# keyboard.net
KiCad netlist of a schematic drawn in EAGLE
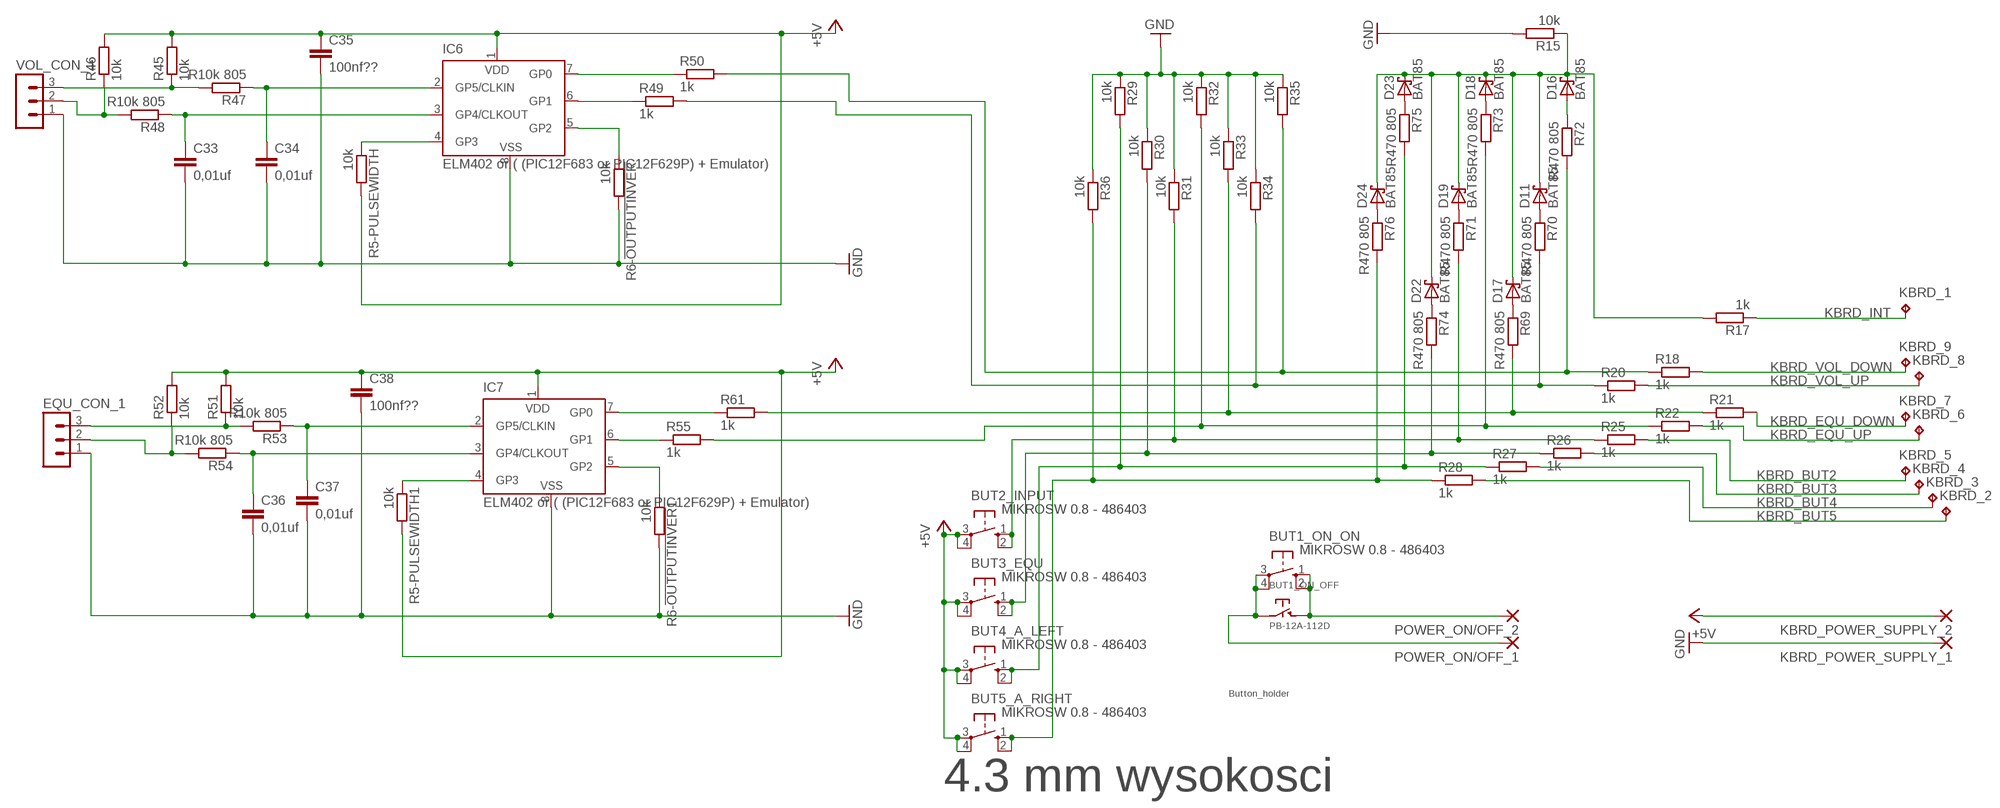
[diagram p0: schematic, sheet 1]

(export (version "E")
  (design (tool "Eeschema 10.0.6"))
  (components
    (comp (ref "BUT1_ON_OFF")
      (value "PB-12A-112D")
      (footprint "eagle-import:PB-12A-112D")
      (libsource (lib "eagle-import") (part "PB-12A-112D"))
    )
    (comp (ref "BUT1_ON_ON")
      (value "MIKROSW 0.8 - 486403")
      (footprint "eagle-import:B3F-10XX")
      (fields
        (field (name "MPN") "B3F-1000")
        (field (name "MF") "OMRON ELECTRONIC COMPONENTS")
        (field (name "MPN_1") "B3F-1000")
        (field (name "OC_FARNELL") "176432")
        (field (name "OC_NEWARK") "36M3542")
      )
      (libsource (lib "eagle-import") (part "10-XX"))
    )
    (comp (ref "BUT2_INPUT")
      (value "MIKROSW 0.8 - 486403")
      (footprint "eagle-import:B3F-10XX")
      (fields
        (field (name "MPN") "B3F-1000")
        (field (name "MF") "OMRON ELECTRONIC COMPONENTS")
        (field (name "MPN_1") "B3F-1000")
        (field (name "OC_FARNELL") "176432")
      )
      (libsource (lib "eagle-import") (part "10-XX"))
    )
    (comp (ref "BUT3_EQU")
      (value "MIKROSW 0.8 - 486403")
      (footprint "eagle-import:B3F-10XX")
      (fields
        (field (name "MPN") "B3F-1000")
        (field (name "MF") "OMRON ELECTRONIC COMPONENTS")
        (field (name "MPN_1") "B3F-1000")
        (field (name "OC_FARNELL") "176432")
      )
      (libsource (lib "eagle-import") (part "10-XX"))
    )
    (comp (ref "BUT4_A_LEFT")
      (value "MIKROSW 0.8 - 486403")
      (footprint "eagle-import:B3F-10XX")
      (fields
        (field (name "MPN") "B3F-1000")
        (field (name "MF") "OMRON ELECTRONIC COMPONENTS")
        (field (name "MPN_1") "B3F-1000")
        (field (name "OC_FARNELL") "176432")
      )
      (libsource (lib "eagle-import") (part "10-XX"))
    )
    (comp (ref "BUT5_A_RIGHT")
      (value "MIKROSW 0.8 - 486403")
      (footprint "eagle-import:B3F-10XX")
      (fields
        (field (name "MPN") "B3F-1000")
        (field (name "MF") "OMRON ELECTRONIC COMPONENTS")
        (field (name "MPN_1") "B3F-1000")
        (field (name "OC_FARNELL") "176432")
      )
      (libsource (lib "eagle-import") (part "10-XX"))
    )
    (comp (ref "C33")
      (value "0,01uf")
      (footprint "eagle-import:C0805")
      (libsource (lib "eagle-import") (part "C-EUC0805"))
    )
    (comp (ref "C34")
      (value "0,01uf")
      (footprint "eagle-import:C0805")
      (libsource (lib "eagle-import") (part "C-EUC0805"))
    )
    (comp (ref "C35")
      (value "100nf??")
      (footprint "eagle-import:C0805")
      (libsource (lib "eagle-import") (part "C-EUC0805"))
    )
    (comp (ref "C36")
      (value "0,01uf")
      (footprint "eagle-import:C0805")
      (libsource (lib "eagle-import") (part "C-EUC0805"))
    )
    (comp (ref "C37")
      (value "0,01uf")
      (footprint "eagle-import:C0805")
      (libsource (lib "eagle-import") (part "C-EUC0805"))
    )
    (comp (ref "C38")
      (value "100nf??")
      (footprint "eagle-import:C0805")
      (libsource (lib "eagle-import") (part "C-EUC0805"))
    )
    (comp (ref "D11")
      (value "BAT85")
      (footprint "eagle-import:DO34-5")
      (libsource (lib "eagle-import") (part "BAT85DO34-5"))
    )
    (comp (ref "D16")
      (value "BAT85")
      (footprint "eagle-import:DO34-5")
      (libsource (lib "eagle-import") (part "BAT85DO34-5"))
    )
    (comp (ref "D17")
      (value "BAT85")
      (footprint "eagle-import:DO34-5")
      (libsource (lib "eagle-import") (part "BAT85DO34-5"))
    )
    (comp (ref "D18")
      (value "BAT85")
      (footprint "eagle-import:DO34-5")
      (libsource (lib "eagle-import") (part "BAT85DO34-5"))
    )
    (comp (ref "D19")
      (value "BAT85")
      (footprint "eagle-import:DO34-5")
      (libsource (lib "eagle-import") (part "BAT85DO34-5"))
    )
    (comp (ref "D22")
      (value "BAT85")
      (footprint "eagle-import:DO34-5")
      (libsource (lib "eagle-import") (part "BAT85DO34-5"))
    )
    (comp (ref "D23")
      (value "BAT85")
      (footprint "eagle-import:DO34-5")
      (libsource (lib "eagle-import") (part "BAT85DO34-5"))
    )
    (comp (ref "D24")
      (value "BAT85")
      (footprint "eagle-import:DO34-5")
      (libsource (lib "eagle-import") (part "BAT85DO34-5"))
    )
    (comp (ref "EQU_CON_1")
      (value "MA03-1")
      (footprint "eagle-import:MA03-1")
      (fields (field (name "OC_FARNELL") "unknown"))
      (libsource (lib "eagle-import") (part "MA03-1"))
    )
    (comp (ref "IC6")
      (value "ELM402 or ( (PIC12F683 or PIC12F629P) + Emulator)")
      (footprint "eagle-import:DIL8")
      (fields
        (field (name "MF") "MICROCHIP")
        (field (name "MPN") "PIC12F629-I/P")
        (field (name "MF_1") "MICROCHIP")
        (field (name "MPN_1") "PIC12F629-E/P")
        (field (name "OC_FARNELL") "1292253")
      )
      (libsource (lib "eagle-import") (part "PIC12F6P29"))
    )
    (comp (ref "IC7")
      (value "ELM402 or ( (PIC12F683 or PIC12F629P) + Emulator)")
      (footprint "eagle-import:DIL8")
      (fields
        (field (name "MF") "MICROCHIP")
        (field (name "MPN") "PIC12F629-I/P")
        (field (name "MF_1") "MICROCHIP")
        (field (name "MPN_1") "PIC12F629-E/P")
        (field (name "OC_FARNELL") "1292253")
      )
      (libsource (lib "eagle-import") (part "PIC12F6P29"))
    )
    (comp (ref "KBRD_1")
      (value "TPPAD1-13Y")
      (footprint "eagle-import:P1-13Y")
      (libsource (lib "eagle-import") (part "TPPAD1-13Y"))
    )
    (comp (ref "KBRD_2")
      (value "TPPAD1-13Y")
      (footprint "eagle-import:P1-13Y")
      (libsource (lib "eagle-import") (part "TPPAD1-13Y"))
    )
    (comp (ref "KBRD_3")
      (value "TPPAD1-13Y")
      (footprint "eagle-import:P1-13Y")
      (libsource (lib "eagle-import") (part "TPPAD1-13Y"))
    )
    (comp (ref "KBRD_4")
      (value "TPPAD1-13Y")
      (footprint "eagle-import:P1-13Y")
      (libsource (lib "eagle-import") (part "TPPAD1-13Y"))
    )
    (comp (ref "KBRD_5")
      (value "TPPAD1-13Y")
      (footprint "eagle-import:P1-13Y")
      (libsource (lib "eagle-import") (part "TPPAD1-13Y"))
    )
    (comp (ref "KBRD_6")
      (value "TPPAD1-13Y")
      (footprint "eagle-import:P1-13Y")
      (libsource (lib "eagle-import") (part "TPPAD1-13Y"))
    )
    (comp (ref "KBRD_7")
      (value "TPPAD1-13Y")
      (footprint "eagle-import:P1-13Y")
      (libsource (lib "eagle-import") (part "TPPAD1-13Y"))
    )
    (comp (ref "KBRD_8")
      (value "TPPAD1-13Y")
      (footprint "eagle-import:P1-13Y")
      (libsource (lib "eagle-import") (part "TPPAD1-13Y"))
    )
    (comp (ref "KBRD_9")
      (value "TPPAD1-13Y")
      (footprint "eagle-import:P1-13Y")
      (libsource (lib "eagle-import") (part "TPPAD1-13Y"))
    )
    (comp (ref "KBRD_POWER_SUPPLY_1")
      (value "1,6/0,9")
      (footprint "eagle-import:1,6_0,9")
      (libsource (lib "eagle-import") (part "1,6/0,9"))
    )
    (comp (ref "KBRD_POWER_SUPPLY_2")
      (value "1,6/0,9")
      (footprint "eagle-import:1,6_0,9")
      (libsource (lib "eagle-import") (part "1,6/0,9"))
    )
    (comp (ref "POWER_ON/OFF_1")
      (value "2,15/1,0")
      (footprint "eagle-import:2,15_1,0")
      (libsource (lib "eagle-import") (part "2,15/1,0"))
    )
    (comp (ref "POWER_ON/OFF_2")
      (value "2,15/1,0")
      (footprint "eagle-import:2,15_1,0")
      (libsource (lib "eagle-import") (part "2,15/1,0"))
    )
    (comp (ref "R5-PULSEWIDTH")
      (value "10k")
      (footprint "eagle-import:0204_7")
      (libsource (lib "eagle-import") (part "resistor_R-EU_0204/7"))
    )
    (comp (ref "R5-PULSEWIDTH1")
      (value "10k")
      (footprint "eagle-import:0204_7")
      (libsource (lib "eagle-import") (part "resistor_R-EU_0204/7"))
    )
    (comp (ref "R6-!OUTPUTINVER!")
      (value "10k")
      (footprint "eagle-import:R0805")
      (libsource (lib "eagle-import") (part "resistor_R-EU_R0805"))
    )
    (comp (ref "R6-!OUTPUTINVER!1")
      (value "10k")
      (footprint "eagle-import:R0805")
      (libsource (lib "eagle-import") (part "resistor_R-EU_R0805"))
    )
    (comp (ref "R15")
      (value "10k")
      (footprint "eagle-import:R0805")
      (libsource (lib "eagle-import") (part "R-EU_R0805"))
    )
    (comp (ref "R17")
      (value "1k")
      (footprint "eagle-import:R0805")
      (libsource (lib "eagle-import") (part "R-EU_R0805"))
    )
    (comp (ref "R18")
      (value "1k")
      (footprint "eagle-import:R0805")
      (libsource (lib "eagle-import") (part "R-EU_R0805"))
    )
    (comp (ref "R20")
      (value "1k")
      (footprint "eagle-import:R0805")
      (libsource (lib "eagle-import") (part "R-EU_R0805"))
    )
    (comp (ref "R21")
      (value "1k")
      (footprint "eagle-import:R0805")
      (libsource (lib "eagle-import") (part "R-EU_R0805"))
    )
    (comp (ref "R22")
      (value "1k")
      (footprint "eagle-import:R0805")
      (libsource (lib "eagle-import") (part "R-EU_R0805"))
    )
    (comp (ref "R25")
      (value "1k")
      (footprint "eagle-import:R0805")
      (libsource (lib "eagle-import") (part "R-EU_R0805"))
    )
    (comp (ref "R26")
      (value "1k")
      (footprint "eagle-import:R0805")
      (libsource (lib "eagle-import") (part "R-EU_R0805"))
    )
    (comp (ref "R27")
      (value "1k")
      (footprint "eagle-import:R0805")
      (libsource (lib "eagle-import") (part "R-EU_R0805"))
    )
    (comp (ref "R28")
      (value "1k")
      (footprint "eagle-import:R0805")
      (libsource (lib "eagle-import") (part "R-EU_R0805"))
    )
    (comp (ref "R29")
      (value "10k")
      (footprint "eagle-import:R0805")
      (libsource (lib "eagle-import") (part "R-EU_R0805"))
    )
    (comp (ref "R30")
      (value "10k")
      (footprint "eagle-import:R0805")
      (libsource (lib "eagle-import") (part "R-EU_R0805"))
    )
    (comp (ref "R31")
      (value "10k")
      (footprint "eagle-import:M0805")
      (libsource (lib "eagle-import") (part "R-EU_M0805"))
    )
    (comp (ref "R32")
      (value "10k")
      (footprint "eagle-import:0204_5")
      (libsource (lib "eagle-import") (part "R-EU_0204/5"))
    )
    (comp (ref "R33")
      (value "10k")
      (footprint "eagle-import:0204_5")
      (libsource (lib "eagle-import") (part "R-EU_0204/5"))
    )
    (comp (ref "R34")
      (value "10k")
      (footprint "eagle-import:0204_5")
      (libsource (lib "eagle-import") (part "R-EU_0204/5"))
    )
    (comp (ref "R35")
      (value "10k")
      (footprint "eagle-import:0204_5")
      (libsource (lib "eagle-import") (part "R-EU_0204/5"))
    )
    (comp (ref "R36")
      (value "10k")
      (footprint "eagle-import:R0805")
      (libsource (lib "eagle-import") (part "R-EU_R0805"))
    )
    (comp (ref "R45")
      (value "10k")
      (footprint "eagle-import:R0805")
      (libsource (lib "eagle-import") (part "resistor_R-EU_R0805"))
    )
    (comp (ref "R46")
      (value "10k")
      (footprint "eagle-import:R0805")
      (libsource (lib "eagle-import") (part "resistor_R-EU_R0805"))
    )
    (comp (ref "R47")
      (value "R10k 805")
      (footprint "eagle-import:R0805")
      (libsource (lib "eagle-import") (part "resistor_R-EU_R0805"))
    )
    (comp (ref "R48")
      (value "R10k 805")
      (footprint "eagle-import:R0805")
      (libsource (lib "eagle-import") (part "resistor_R-EU_R0805"))
    )
    (comp (ref "R49")
      (value "1k")
      (footprint "eagle-import:R0805")
      (libsource (lib "eagle-import") (part "resistor_R-EU_R0805"))
    )
    (comp (ref "R50")
      (value "1k")
      (footprint "eagle-import:R0805")
      (libsource (lib "eagle-import") (part "resistor_R-EU_R0805"))
    )
    (comp (ref "R51")
      (value "10k")
      (footprint "eagle-import:M0805")
      (libsource (lib "eagle-import") (part "resistor_R-EU_M0805"))
    )
    (comp (ref "R52")
      (value "10k")
      (footprint "eagle-import:M0805")
      (libsource (lib "eagle-import") (part "resistor_R-EU_M0805"))
    )
    (comp (ref "R53")
      (value "R10k 805")
      (footprint "eagle-import:R0805")
      (libsource (lib "eagle-import") (part "resistor_R-EU_R0805"))
    )
    (comp (ref "R54")
      (value "R10k 805")
      (footprint "eagle-import:R0805")
      (libsource (lib "eagle-import") (part "resistor_R-EU_R0805"))
    )
    (comp (ref "R55")
      (value "1k")
      (footprint "eagle-import:R0805")
      (libsource (lib "eagle-import") (part "resistor_R-EU_R0805"))
    )
    (comp (ref "R61")
      (value "1k")
      (footprint "eagle-import:R0805")
      (libsource (lib "eagle-import") (part "resistor_R-EU_R0805"))
    )
    (comp (ref "R69")
      (value "R470 805")
      (footprint "eagle-import:R0805")
      (libsource (lib "eagle-import") (part "R-EU_R0805"))
    )
    (comp (ref "R70")
      (value "R470 805")
      (footprint "eagle-import:R0805")
      (libsource (lib "eagle-import") (part "R-EU_R0805"))
    )
    (comp (ref "R71")
      (value "R470 805")
      (footprint "eagle-import:R0805")
      (libsource (lib "eagle-import") (part "R-EU_R0805"))
    )
    (comp (ref "R72")
      (value "R470 805")
      (footprint "eagle-import:R0805")
      (libsource (lib "eagle-import") (part "R-EU_R0805"))
    )
    (comp (ref "R73")
      (value "R470 805")
      (footprint "eagle-import:R0805")
      (libsource (lib "eagle-import") (part "R-EU_R0805"))
    )
    (comp (ref "R74")
      (value "R470 805")
      (footprint "eagle-import:R0805")
      (libsource (lib "eagle-import") (part "R-EU_R0805"))
    )
    (comp (ref "R75")
      (value "R470 805")
      (footprint "eagle-import:R0805")
      (libsource (lib "eagle-import") (part "R-EU_R0805"))
    )
    (comp (ref "R76")
      (value "R470 805")
      (footprint "eagle-import:R0805")
      (libsource (lib "eagle-import") (part "R-EU_R0805"))
    )
    (comp (ref "U$1")
      (value "TRZYMADLO")
      (footprint "eagle-import:TRZYMADLO_POPYCHACZY")
      (libsource (lib "eagle-import") (part "TRZYMADLO"))
    )
    (comp (ref "VOL_CON_1")
      (value "MA03-1")
      (footprint "eagle-import:MA03-1")
      (fields (field (name "OC_FARNELL") "unknown"))
      (libsource (lib "eagle-import") (part "MA03-1"))
    )
  )
  (nets
    (net (code "1") (name "+5V") (class "Default")
      (node (ref "BUT2_INPUT") (pin "3") (pinfunction "P_3") (pintype "passive"))
      (node (ref "BUT2_INPUT") (pin "4") (pinfunction "P1_4") (pintype "passive"))
      (node (ref "BUT3_EQU") (pin "3") (pinfunction "P_3") (pintype "passive"))
      (node (ref "BUT3_EQU") (pin "4") (pinfunction "P1_4") (pintype "passive"))
      (node (ref "BUT4_A_LEFT") (pin "3") (pinfunction "P_3") (pintype "passive"))
      (node (ref "BUT4_A_LEFT") (pin "4") (pinfunction "P1_4") (pintype "passive"))
      (node (ref "BUT5_A_RIGHT") (pin "3") (pinfunction "P_3") (pintype "passive"))
      (node (ref "BUT5_A_RIGHT") (pin "4") (pinfunction "P1_4") (pintype "passive"))
      (node (ref "C35") (pin "1") (pinfunction "1_1") (pintype "passive"))
      (node (ref "C38") (pin "1") (pinfunction "1_1") (pintype "passive"))
      (node (ref "IC6") (pin "1") (pinfunction "VDD_1") (pintype "power_in"))
      (node (ref "IC7") (pin "1") (pinfunction "VDD_1") (pintype "power_in"))
      (node (ref "KBRD_POWER_SUPPLY_2") (pin "1") (pinfunction "P_1") (pintype "passive"))
      (node (ref "R45") (pin "2") (pinfunction "2_2") (pintype "passive"))
      (node (ref "R46") (pin "2") (pinfunction "2_2") (pintype "passive"))
      (node (ref "R5-PULSEWIDTH") (pin "2") (pinfunction "2_2") (pintype "passive"))
      (node (ref "R5-PULSEWIDTH1") (pin "2") (pinfunction "2_2") (pintype "passive"))
      (node (ref "R51") (pin "2") (pinfunction "2_2") (pintype "passive"))
      (node (ref "R52") (pin "2") (pinfunction "2_2") (pintype "passive"))
    )
    (net (code "2") (name "/KBRD_BUT2") (class "Default")
      (node (ref "KBRD_5") (pin "TP") (pinfunction "TP_TP") (pintype "input"))
      (node (ref "R25") (pin "2") (pinfunction "2_2") (pintype "passive"))
    )
    (net (code "3") (name "/KBRD_BUT3") (class "Default")
      (node (ref "KBRD_4") (pin "TP") (pinfunction "TP_TP") (pintype "input"))
      (node (ref "R26") (pin "2") (pinfunction "2_2") (pintype "passive"))
    )
    (net (code "4") (name "/KBRD_BUT4") (class "Default")
      (node (ref "KBRD_3") (pin "TP") (pinfunction "TP_TP") (pintype "input"))
      (node (ref "R27") (pin "2") (pinfunction "2_2") (pintype "passive"))
    )
    (net (code "5") (name "/KBRD_BUT5") (class "Default")
      (node (ref "KBRD_2") (pin "TP") (pinfunction "TP_TP") (pintype "input"))
      (node (ref "R28") (pin "2") (pinfunction "2_2") (pintype "passive"))
    )
    (net (code "6") (name "/KBRD_EQU_DOWN") (class "Default")
      (node (ref "KBRD_7") (pin "TP") (pinfunction "TP_TP") (pintype "input"))
      (node (ref "R21") (pin "2") (pinfunction "2_2") (pintype "passive"))
    )
    (net (code "7") (name "/KBRD_EQU_UP") (class "Default")
      (node (ref "KBRD_6") (pin "TP") (pinfunction "TP_TP") (pintype "input"))
      (node (ref "R22") (pin "2") (pinfunction "2_2") (pintype "passive"))
    )
    (net (code "8") (name "/KBRD_INT") (class "Default")
      (node (ref "KBRD_1") (pin "TP") (pinfunction "TP_TP") (pintype "input"))
      (node (ref "R17") (pin "1") (pinfunction "1_1") (pintype "passive"))
    )
    (net (code "9") (name "/KBRD_VOL_DOWN") (class "Default")
      (node (ref "KBRD_9") (pin "TP") (pinfunction "TP_TP") (pintype "input"))
      (node (ref "R18") (pin "2") (pinfunction "2_2") (pintype "passive"))
    )
    (net (code "10") (name "/KBRD_VOL_UP") (class "Default")
      (node (ref "KBRD_8") (pin "TP") (pinfunction "TP_TP") (pintype "input"))
      (node (ref "R20") (pin "2") (pinfunction "2_2") (pintype "passive"))
    )
    (net (code "11") (name "GND") (class "Default")
      (node (ref "C33") (pin "2") (pinfunction "2_2") (pintype "passive"))
      (node (ref "C34") (pin "2") (pinfunction "2_2") (pintype "passive"))
      (node (ref "C35") (pin "2") (pinfunction "2_2") (pintype "passive"))
      (node (ref "C36") (pin "2") (pinfunction "2_2") (pintype "passive"))
      (node (ref "C37") (pin "2") (pinfunction "2_2") (pintype "passive"))
      (node (ref "C38") (pin "2") (pinfunction "2_2") (pintype "passive"))
      (node (ref "EQU_CON_1") (pin "1") (pinfunction "1_1") (pintype "passive"))
      (node (ref "IC6") (pin "8") (pinfunction "VSS_8") (pintype "power_in"))
      (node (ref "IC7") (pin "8") (pinfunction "VSS_8") (pintype "power_in"))
      (node (ref "KBRD_POWER_SUPPLY_1") (pin "1") (pinfunction "P_1") (pintype "passive"))
      (node (ref "R15") (pin "2") (pinfunction "2_2") (pintype "passive"))
      (node (ref "R29") (pin "1") (pinfunction "1_1") (pintype "passive"))
      (node (ref "R30") (pin "1") (pinfunction "1_1") (pintype "passive"))
      (node (ref "R31") (pin "1") (pinfunction "1_1") (pintype "passive"))
      (node (ref "R32") (pin "1") (pinfunction "1_1") (pintype "passive"))
      (node (ref "R33") (pin "1") (pinfunction "1_1") (pintype "passive"))
      (node (ref "R34") (pin "1") (pinfunction "1_1") (pintype "passive"))
      (node (ref "R35") (pin "1") (pinfunction "1_1") (pintype "passive"))
      (node (ref "R36") (pin "1") (pinfunction "1_1") (pintype "passive"))
      (node (ref "R6-!OUTPUTINVER!") (pin "2") (pinfunction "2_2") (pintype "passive"))
      (node (ref "R6-!OUTPUTINVER!1") (pin "2") (pinfunction "2_2") (pintype "passive"))
      (node (ref "VOL_CON_1") (pin "1") (pinfunction "1_1") (pintype "passive"))
    )
    (net (code "12") (name "Net-(BUT1_ON_ON-P)") (class "Default")
      (node (ref "BUT1_ON_OFF") (pin "P$1") (pinfunction "P$1_P$1") (pintype "bidirectional"))
      (node (ref "BUT1_ON_ON") (pin "3") (pinfunction "P_3") (pintype "passive"))
      (node (ref "BUT1_ON_ON") (pin "4") (pinfunction "P1_4") (pintype "passive"))
      (node (ref "POWER_ON/OFF_1") (pin "1") (pinfunction "P_1") (pintype "passive"))
    )
    (net (code "13") (name "Net-(BUT1_ON_ON-S)") (class "Default")
      (node (ref "BUT1_ON_OFF") (pin "P$2") (pinfunction "P$2_P$2") (pintype "bidirectional"))
      (node (ref "BUT1_ON_ON") (pin "1") (pinfunction "S_1") (pintype "passive"))
      (node (ref "BUT1_ON_ON") (pin "2") (pinfunction "S1_2") (pintype "passive"))
      (node (ref "POWER_ON/OFF_2") (pin "1") (pinfunction "P_1") (pintype "passive"))
    )
    (net (code "14") (name "Net-(BUT2_INPUT-S)") (class "Default")
      (node (ref "BUT2_INPUT") (pin "1") (pinfunction "S_1") (pintype "passive"))
      (node (ref "BUT2_INPUT") (pin "2") (pinfunction "S1_2") (pintype "passive"))
      (node (ref "R25") (pin "1") (pinfunction "1_1") (pintype "passive"))
      (node (ref "R31") (pin "2") (pinfunction "2_2") (pintype "passive"))
      (node (ref "R71") (pin "2") (pinfunction "2_2") (pintype "passive"))
    )
    (net (code "15") (name "Net-(BUT3_EQU-S)") (class "Default")
      (node (ref "BUT3_EQU") (pin "1") (pinfunction "S_1") (pintype "passive"))
      (node (ref "BUT3_EQU") (pin "2") (pinfunction "S1_2") (pintype "passive"))
      (node (ref "R26") (pin "1") (pinfunction "1_1") (pintype "passive"))
      (node (ref "R30") (pin "2") (pinfunction "2_2") (pintype "passive"))
      (node (ref "R74") (pin "2") (pinfunction "2_2") (pintype "passive"))
    )
    (net (code "16") (name "Net-(BUT4_A_LEFT-S)") (class "Default")
      (node (ref "BUT4_A_LEFT") (pin "1") (pinfunction "S_1") (pintype "passive"))
      (node (ref "BUT4_A_LEFT") (pin "2") (pinfunction "S1_2") (pintype "passive"))
      (node (ref "R27") (pin "1") (pinfunction "1_1") (pintype "passive"))
      (node (ref "R29") (pin "2") (pinfunction "2_2") (pintype "passive"))
      (node (ref "R75") (pin "2") (pinfunction "2_2") (pintype "passive"))
    )
    (net (code "17") (name "Net-(BUT5_A_RIGHT-S)") (class "Default")
      (node (ref "BUT5_A_RIGHT") (pin "1") (pinfunction "S_1") (pintype "passive"))
      (node (ref "BUT5_A_RIGHT") (pin "2") (pinfunction "S1_2") (pintype "passive"))
      (node (ref "R28") (pin "1") (pinfunction "1_1") (pintype "passive"))
      (node (ref "R36") (pin "2") (pinfunction "2_2") (pintype "passive"))
      (node (ref "R76") (pin "2") (pinfunction "2_2") (pintype "passive"))
    )
    (net (code "18") (name "Net-(D11-PadA)") (class "Default")
      (node (ref "D11") (pin "A") (pinfunction "A_A") (pintype "passive"))
      (node (ref "R70") (pin "1") (pinfunction "1_1") (pintype "passive"))
    )
    (net (code "19") (name "Net-(D11-PadC)") (class "Default")
      (node (ref "D11") (pin "C") (pinfunction "C_C") (pintype "passive"))
      (node (ref "D16") (pin "C") (pinfunction "C_C") (pintype "passive"))
      (node (ref "D17") (pin "C") (pinfunction "C_C") (pintype "passive"))
      (node (ref "D18") (pin "C") (pinfunction "C_C") (pintype "passive"))
      (node (ref "D19") (pin "C") (pinfunction "C_C") (pintype "passive"))
      (node (ref "D22") (pin "C") (pinfunction "C_C") (pintype "passive"))
      (node (ref "D23") (pin "C") (pinfunction "C_C") (pintype "passive"))
      (node (ref "D24") (pin "C") (pinfunction "C_C") (pintype "passive"))
      (node (ref "R15") (pin "1") (pinfunction "1_1") (pintype "passive"))
      (node (ref "R17") (pin "2") (pinfunction "2_2") (pintype "passive"))
    )
    (net (code "20") (name "Net-(D16-PadA)") (class "Default")
      (node (ref "D16") (pin "A") (pinfunction "A_A") (pintype "passive"))
      (node (ref "R72") (pin "1") (pinfunction "1_1") (pintype "passive"))
    )
    (net (code "21") (name "Net-(D17-PadA)") (class "Default")
      (node (ref "D17") (pin "A") (pinfunction "A_A") (pintype "passive"))
      (node (ref "R69") (pin "1") (pinfunction "1_1") (pintype "passive"))
    )
    (net (code "22") (name "Net-(D18-PadA)") (class "Default")
      (node (ref "D18") (pin "A") (pinfunction "A_A") (pintype "passive"))
      (node (ref "R73") (pin "1") (pinfunction "1_1") (pintype "passive"))
    )
    (net (code "23") (name "Net-(D19-PadA)") (class "Default")
      (node (ref "D19") (pin "A") (pinfunction "A_A") (pintype "passive"))
      (node (ref "R71") (pin "1") (pinfunction "1_1") (pintype "passive"))
    )
    (net (code "24") (name "Net-(D22-PadA)") (class "Default")
      (node (ref "D22") (pin "A") (pinfunction "A_A") (pintype "passive"))
      (node (ref "R74") (pin "1") (pinfunction "1_1") (pintype "passive"))
    )
    (net (code "25") (name "Net-(D23-PadA)") (class "Default")
      (node (ref "D23") (pin "A") (pinfunction "A_A") (pintype "passive"))
      (node (ref "R75") (pin "1") (pinfunction "1_1") (pintype "passive"))
    )
    (net (code "26") (name "Net-(D24-PadA)") (class "Default")
      (node (ref "D24") (pin "A") (pinfunction "A_A") (pintype "passive"))
      (node (ref "R76") (pin "1") (pinfunction "1_1") (pintype "passive"))
    )
    (net (code "27") (name "Net-(EQU_CON_1-Pad2)") (class "Default")
      (node (ref "EQU_CON_1") (pin "2") (pinfunction "2_2") (pintype "passive"))
      (node (ref "R52") (pin "1") (pinfunction "1_1") (pintype "passive"))
      (node (ref "R54") (pin "2") (pinfunction "2_2") (pintype "passive"))
    )
    (net (code "28") (name "Net-(EQU_CON_1-Pad3)") (class "Default")
      (node (ref "EQU_CON_1") (pin "3") (pinfunction "3_3") (pintype "passive"))
      (node (ref "R51") (pin "1") (pinfunction "1_1") (pintype "passive"))
      (node (ref "R53") (pin "2") (pinfunction "2_2") (pintype "passive"))
    )
    (net (code "29") (name "Net-(IC6-GP0)") (class "Default")
      (node (ref "IC6") (pin "7") (pinfunction "GP0_7") (pintype "bidirectional"))
      (node (ref "R50") (pin "1") (pinfunction "1_1") (pintype "passive"))
    )
    (net (code "30") (name "Net-(IC6-GP1)") (class "Default")
      (node (ref "IC6") (pin "6") (pinfunction "GP1_6") (pintype "bidirectional"))
      (node (ref "R49") (pin "1") (pinfunction "1_1") (pintype "passive"))
    )
    (net (code "31") (name "Net-(IC6-GP2)") (class "Default")
      (node (ref "IC6") (pin "5") (pinfunction "GP2_5") (pintype "bidirectional"))
      (node (ref "R6-!OUTPUTINVER!") (pin "1") (pinfunction "1_1") (pintype "passive"))
    )
    (net (code "32") (name "Net-(IC6-GP3)") (class "Default")
      (node (ref "IC6") (pin "4") (pinfunction "GP3_4") (pintype "input"))
      (node (ref "R5-PULSEWIDTH") (pin "1") (pinfunction "1_1") (pintype "passive"))
    )
    (net (code "33") (name "Net-(IC6-GP4{slash}CLKOUT)") (class "Default")
      (node (ref "C33") (pin "1") (pinfunction "1_1") (pintype "passive"))
      (node (ref "IC6") (pin "3") (pinfunction "GP4/CLKOUT_3") (pintype "bidirectional"))
      (node (ref "R48") (pin "1") (pinfunction "1_1") (pintype "passive"))
    )
    (net (code "34") (name "Net-(IC6-GP5{slash}CLKIN)") (class "Default")
      (node (ref "C34") (pin "1") (pinfunction "1_1") (pintype "passive"))
      (node (ref "IC6") (pin "2") (pinfunction "GP5/CLKIN_2") (pintype "bidirectional"))
      (node (ref "R47") (pin "1") (pinfunction "1_1") (pintype "passive"))
    )
    (net (code "35") (name "Net-(IC7-GP0)") (class "Default")
      (node (ref "IC7") (pin "7") (pinfunction "GP0_7") (pintype "bidirectional"))
      (node (ref "R61") (pin "1") (pinfunction "1_1") (pintype "passive"))
    )
    (net (code "36") (name "Net-(IC7-GP1)") (class "Default")
      (node (ref "IC7") (pin "6") (pinfunction "GP1_6") (pintype "bidirectional"))
      (node (ref "R55") (pin "1") (pinfunction "1_1") (pintype "passive"))
    )
    (net (code "37") (name "Net-(IC7-GP2)") (class "Default")
      (node (ref "IC7") (pin "5") (pinfunction "GP2_5") (pintype "bidirectional"))
      (node (ref "R6-!OUTPUTINVER!1") (pin "1") (pinfunction "1_1") (pintype "passive"))
    )
    (net (code "38") (name "Net-(IC7-GP3)") (class "Default")
      (node (ref "IC7") (pin "4") (pinfunction "GP3_4") (pintype "input"))
      (node (ref "R5-PULSEWIDTH1") (pin "1") (pinfunction "1_1") (pintype "passive"))
    )
    (net (code "39") (name "Net-(IC7-GP4{slash}CLKOUT)") (class "Default")
      (node (ref "C36") (pin "1") (pinfunction "1_1") (pintype "passive"))
      (node (ref "IC7") (pin "3") (pinfunction "GP4/CLKOUT_3") (pintype "bidirectional"))
      (node (ref "R54") (pin "1") (pinfunction "1_1") (pintype "passive"))
    )
    (net (code "40") (name "Net-(IC7-GP5{slash}CLKIN)") (class "Default")
      (node (ref "C37") (pin "1") (pinfunction "1_1") (pintype "passive"))
      (node (ref "IC7") (pin "2") (pinfunction "GP5/CLKIN_2") (pintype "bidirectional"))
      (node (ref "R53") (pin "1") (pinfunction "1_1") (pintype "passive"))
    )
    (net (code "41") (name "Net-(R18-Pad1)") (class "Default")
      (node (ref "R18") (pin "1") (pinfunction "1_1") (pintype "passive"))
      (node (ref "R35") (pin "2") (pinfunction "2_2") (pintype "passive"))
      (node (ref "R50") (pin "2") (pinfunction "2_2") (pintype "passive"))
      (node (ref "R72") (pin "2") (pinfunction "2_2") (pintype "passive"))
    )
    (net (code "42") (name "Net-(R20-Pad1)") (class "Default")
      (node (ref "R20") (pin "1") (pinfunction "1_1") (pintype "passive"))
      (node (ref "R34") (pin "2") (pinfunction "2_2") (pintype "passive"))
      (node (ref "R49") (pin "2") (pinfunction "2_2") (pintype "passive"))
      (node (ref "R70") (pin "2") (pinfunction "2_2") (pintype "passive"))
    )
    (net (code "43") (name "Net-(R21-Pad1)") (class "Default")
      (node (ref "R21") (pin "1") (pinfunction "1_1") (pintype "passive"))
      (node (ref "R33") (pin "2") (pinfunction "2_2") (pintype "passive"))
      (node (ref "R61") (pin "2") (pinfunction "2_2") (pintype "passive"))
      (node (ref "R69") (pin "2") (pinfunction "2_2") (pintype "passive"))
    )
    (net (code "44") (name "Net-(R22-Pad1)") (class "Default")
      (node (ref "R22") (pin "1") (pinfunction "1_1") (pintype "passive"))
      (node (ref "R32") (pin "2") (pinfunction "2_2") (pintype "passive"))
      (node (ref "R55") (pin "2") (pinfunction "2_2") (pintype "passive"))
      (node (ref "R73") (pin "2") (pinfunction "2_2") (pintype "passive"))
    )
    (net (code "45") (name "Net-(R45-Pad1)") (class "Default")
      (node (ref "R45") (pin "1") (pinfunction "1_1") (pintype "passive"))
      (node (ref "R47") (pin "2") (pinfunction "2_2") (pintype "passive"))
      (node (ref "VOL_CON_1") (pin "3") (pinfunction "3_3") (pintype "passive"))
    )
    (net (code "46") (name "Net-(R46-Pad1)") (class "Default")
      (node (ref "R46") (pin "1") (pinfunction "1_1") (pintype "passive"))
      (node (ref "R48") (pin "2") (pinfunction "2_2") (pintype "passive"))
      (node (ref "VOL_CON_1") (pin "2") (pinfunction "2_2") (pintype "passive"))
    )
  )
)
